# final_design_v1.net
KiCad netlist of a schematic drawn in EAGLE
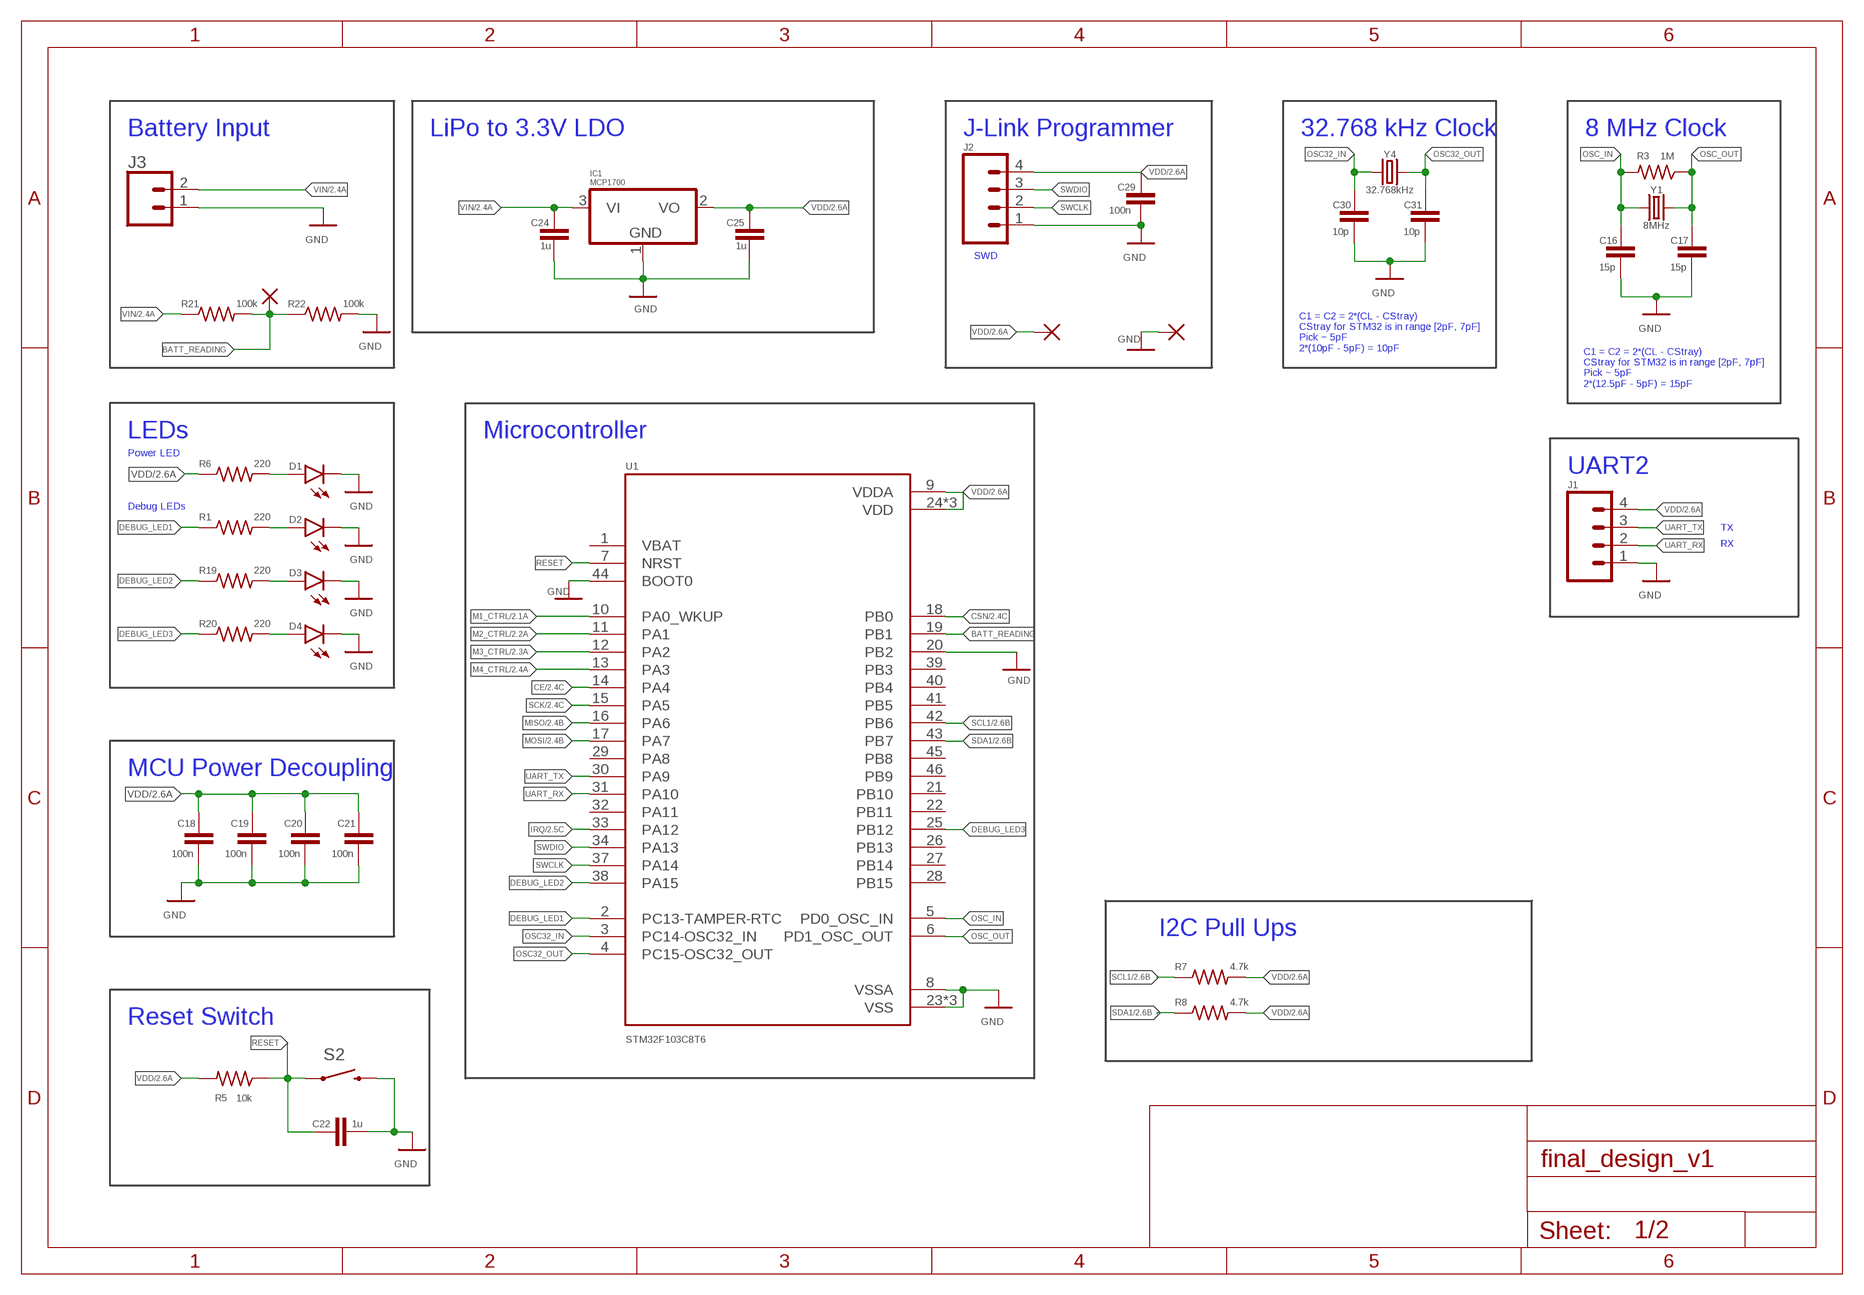
[diagram p0: schematic, sheet 1]
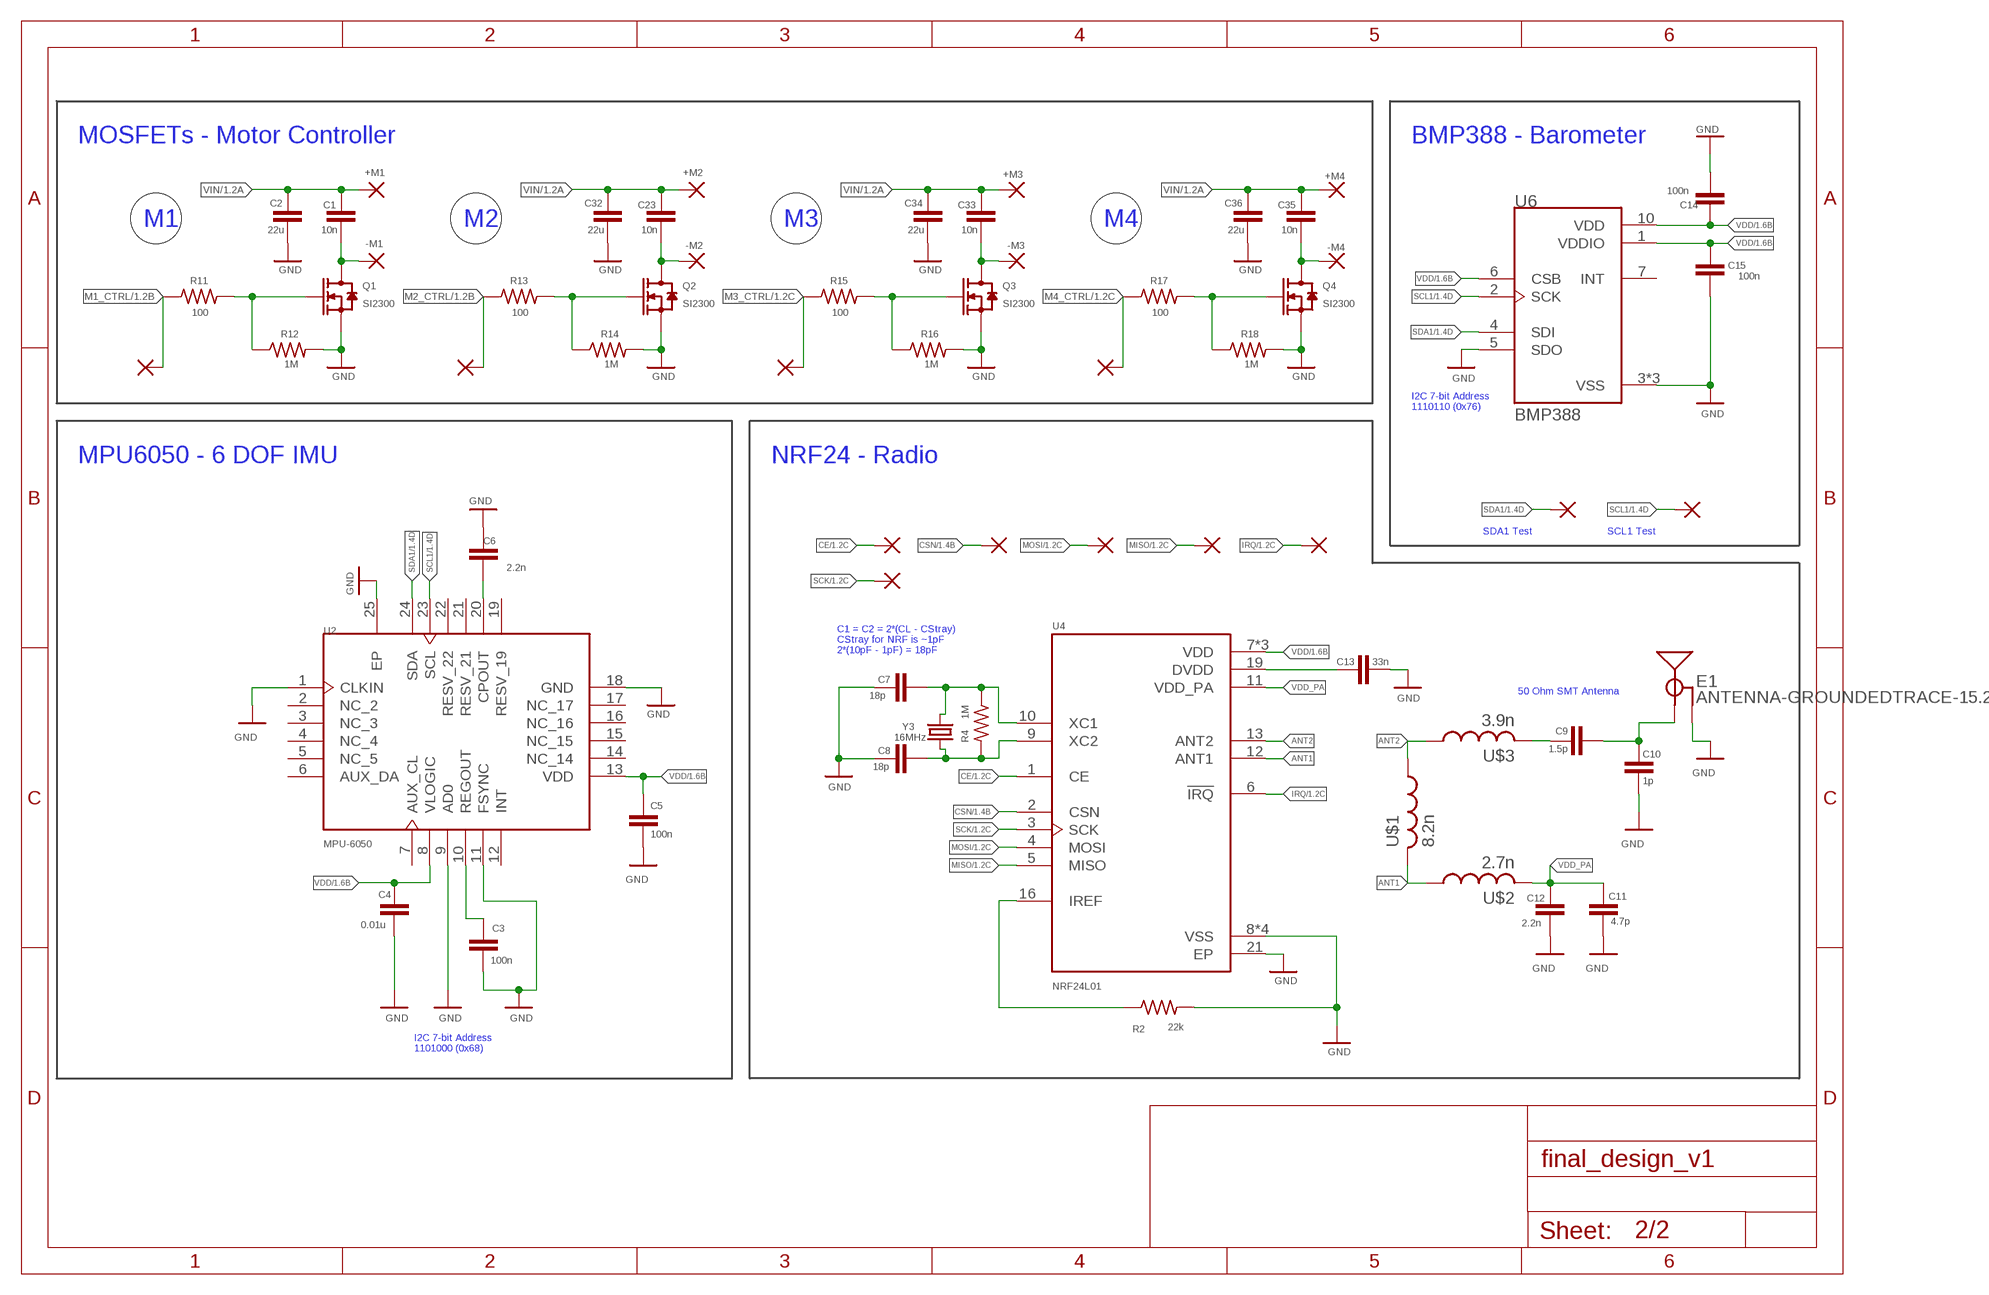
[diagram p1: schematic, sheet 2]

(export (version "E")
  (design (tool "Eeschema 10.0.6"))
  (components
    (comp (ref "+M1")
      (value "SMD2")
      (footprint "eagle-import:SMD1,27-2,54")
      (libsource (lib "eagle-import") (part "SMD2"))
    )
    (comp (ref "+M2")
      (value "SMD2")
      (footprint "eagle-import:SMD1,27-2,54")
      (libsource (lib "eagle-import") (part "SMD2"))
    )
    (comp (ref "+M3")
      (value "SMD2")
      (footprint "eagle-import:SMD1,27-2,54")
      (libsource (lib "eagle-import") (part "SMD2"))
    )
    (comp (ref "+M4")
      (value "SMD2")
      (footprint "eagle-import:SMD1,27-2,54")
      (libsource (lib "eagle-import") (part "SMD2"))
    )
    (comp (ref "+M5")
      (value "SMD2")
      (footprint "eagle-import:SMD1,27-2,54")
      (libsource (lib "eagle-import") (part "SMD2"))
    )
    (comp (ref "+M6")
      (value "SMD2")
      (footprint "eagle-import:SMD1,27-2,54")
      (libsource (lib "eagle-import") (part "SMD2"))
    )
    (comp (ref "+M7")
      (value "SMD2")
      (footprint "eagle-import:SMD1,27-2,54")
      (libsource (lib "eagle-import") (part "SMD2"))
    )
    (comp (ref "+M8")
      (value "SMD2")
      (footprint "eagle-import:SMD1,27-2,54")
      (libsource (lib "eagle-import") (part "SMD2"))
    )
    (comp (ref "+M9")
      (value "SMD2")
      (footprint "eagle-import:SMD1,27-2,54")
      (libsource (lib "eagle-import") (part "SMD2"))
    )
    (comp (ref "+M10")
      (value "SMD2")
      (footprint "eagle-import:SMD1,27-2,54")
      (libsource (lib "eagle-import") (part "SMD2"))
    )
    (comp (ref "+M13")
      (value "SMD2")
      (footprint "eagle-import:SMD1,27-2,54")
      (libsource (lib "eagle-import") (part "SMD2"))
    )
    (comp (ref "+M14")
      (value "SMD2")
      (footprint "eagle-import:SMD1,27-2,54")
      (libsource (lib "eagle-import") (part "SMD2"))
    )
    (comp (ref "+M15")
      (value "SMD2")
      (footprint "eagle-import:SMD1,27-2,54")
      (libsource (lib "eagle-import") (part "SMD2"))
    )
    (comp (ref "+M16")
      (value "SMD2")
      (footprint "eagle-import:SMD1,27-2,54")
      (libsource (lib "eagle-import") (part "SMD2"))
    )
    (comp (ref "+M17")
      (value "SMD2")
      (footprint "eagle-import:SMD1,27-2,54")
      (libsource (lib "eagle-import") (part "SMD2"))
    )
    (comp (ref "+M22")
      (value "SMD2")
      (footprint "eagle-import:SMD1,27-2,54")
      (libsource (lib "eagle-import") (part "SMD2"))
    )
    (comp (ref "-M1")
      (value "SMD2")
      (footprint "eagle-import:SMD1,27-2,54")
      (libsource (lib "eagle-import") (part "SMD2"))
    )
    (comp (ref "-M2")
      (value "SMD2")
      (footprint "eagle-import:SMD1,27-2,54")
      (libsource (lib "eagle-import") (part "SMD2"))
    )
    (comp (ref "-M3")
      (value "SMD2")
      (footprint "eagle-import:SMD1,27-2,54")
      (libsource (lib "eagle-import") (part "SMD2"))
    )
    (comp (ref "-M4")
      (value "SMD2")
      (footprint "eagle-import:SMD1,27-2,54")
      (libsource (lib "eagle-import") (part "SMD2"))
    )
    (comp (ref "C1")
      (value "10n")
      (footprint "eagle-import:CAP_0603")
      (fields
        (field (name "DIGIKEY_PART_NUMBER") "399-7814-2-ND")
        (field (name "MANUFACTURER") "KEMET")
        (field (name "MPN") "C0603C100C5GACTU")
        (field (name "CREATED_BY") "PCBLayout.com")
      )
      (libsource (lib "eagle-import") (part "C0603C100C5GACTU"))
    )
    (comp (ref "C2")
      (value "22u")
      (footprint "eagle-import:CAP_0603")
      (fields
        (field (name "DIGIKEY_PART_NUMBER") "399-7814-2-ND")
        (field (name "MANUFACTURER") "KEMET")
        (field (name "MPN") "C0603C100C5GACTU")
        (field (name "CREATED_BY") "PCBLayout.com")
      )
      (libsource (lib "eagle-import") (part "C0603C100C5GACTU"))
    )
    (comp (ref "C3")
      (value "100n")
      (footprint "eagle-import:CAP_0603")
      (fields
        (field (name "DIGIKEY_PART_NUMBER") "399-7814-2-ND")
        (field (name "MANUFACTURER") "KEMET")
        (field (name "MPN") "C0603C100C5GACTU")
        (field (name "CREATED_BY") "PCBLayout.com")
      )
      (libsource (lib "eagle-import") (part "C0603C100C5GACTU"))
    )
    (comp (ref "C4")
      (value "0.01u")
      (footprint "eagle-import:CAP_0603")
      (fields
        (field (name "DIGIKEY_PART_NUMBER") "399-7814-2-ND")
        (field (name "MANUFACTURER") "KEMET")
        (field (name "MPN") "C0603C100C5GACTU")
        (field (name "CREATED_BY") "PCBLayout.com")
      )
      (libsource (lib "eagle-import") (part "C0603C100C5GACTU"))
    )
    (comp (ref "C5")
      (value "100n")
      (footprint "eagle-import:CAP_0603")
      (fields
        (field (name "DIGIKEY_PART_NUMBER") "399-7814-2-ND")
        (field (name "MANUFACTURER") "KEMET")
        (field (name "MPN") "C0603C100C5GACTU")
        (field (name "CREATED_BY") "PCBLayout.com")
      )
      (libsource (lib "eagle-import") (part "C0603C100C5GACTU"))
    )
    (comp (ref "C6")
      (value "2.2n")
      (footprint "eagle-import:CAP_0603")
      (fields
        (field (name "DIGIKEY_PART_NUMBER") "399-7814-2-ND")
        (field (name "MANUFACTURER") "KEMET")
        (field (name "MPN") "C0603C100C5GACTU")
        (field (name "CREATED_BY") "PCBLayout.com")
      )
      (libsource (lib "eagle-import") (part "C0603C100C5GACTU"))
    )
    (comp (ref "C7")
      (value "18p")
      (footprint "eagle-import:CAP_0603")
      (fields
        (field (name "DIGIKEY_PART_NUMBER") "399-7814-2-ND")
        (field (name "MANUFACTURER") "KEMET")
        (field (name "MPN") "C0603C100C5GACTU")
        (field (name "CREATED_BY") "PCBLayout.com")
      )
      (libsource (lib "eagle-import") (part "C0603C100C5GACTU"))
    )
    (comp (ref "C8")
      (value "18p")
      (footprint "eagle-import:CAP_0603")
      (fields
        (field (name "DIGIKEY_PART_NUMBER") "399-7814-2-ND")
        (field (name "MANUFACTURER") "KEMET")
        (field (name "MPN") "C0603C100C5GACTU")
        (field (name "CREATED_BY") "PCBLayout.com")
      )
      (libsource (lib "eagle-import") (part "C0603C100C5GACTU"))
    )
    (comp (ref "C9")
      (value "1.5p")
      (footprint "eagle-import:CAP_0603")
      (fields
        (field (name "DIGIKEY_PART_NUMBER") "399-7814-2-ND")
        (field (name "MANUFACTURER") "KEMET")
        (field (name "MPN") "C0603C100C5GACTU")
        (field (name "CREATED_BY") "PCBLayout.com")
      )
      (libsource (lib "eagle-import") (part "C0603C100C5GACTU"))
    )
    (comp (ref "C10")
      (value "1p")
      (footprint "eagle-import:CAP_0603")
      (fields
        (field (name "DIGIKEY_PART_NUMBER") "399-7814-2-ND")
        (field (name "MANUFACTURER") "KEMET")
        (field (name "MPN") "C0603C100C5GACTU")
        (field (name "CREATED_BY") "PCBLayout.com")
      )
      (libsource (lib "eagle-import") (part "C0603C100C5GACTU"))
    )
    (comp (ref "C11")
      (value "4.7p")
      (footprint "eagle-import:CAP_0603")
      (fields
        (field (name "DIGIKEY_PART_NUMBER") "399-7814-2-ND")
        (field (name "MANUFACTURER") "KEMET")
        (field (name "MPN") "C0603C100C5GACTU")
        (field (name "CREATED_BY") "PCBLayout.com")
      )
      (libsource (lib "eagle-import") (part "C0603C100C5GACTU"))
    )
    (comp (ref "C12")
      (value "2.2n")
      (footprint "eagle-import:CAP_0603")
      (fields
        (field (name "DIGIKEY_PART_NUMBER") "399-7814-2-ND")
        (field (name "MANUFACTURER") "KEMET")
        (field (name "MPN") "C0603C100C5GACTU")
        (field (name "CREATED_BY") "PCBLayout.com")
      )
      (libsource (lib "eagle-import") (part "C0603C100C5GACTU"))
    )
    (comp (ref "C13")
      (value "33n")
      (footprint "eagle-import:CAP_0603")
      (fields
        (field (name "DIGIKEY_PART_NUMBER") "399-7814-2-ND")
        (field (name "MANUFACTURER") "KEMET")
        (field (name "MPN") "C0603C100C5GACTU")
        (field (name "CREATED_BY") "PCBLayout.com")
      )
      (libsource (lib "eagle-import") (part "C0603C100C5GACTU"))
    )
    (comp (ref "C14")
      (value "100n")
      (footprint "eagle-import:CAP_0603")
      (fields
        (field (name "DIGIKEY_PART_NUMBER") "399-7814-2-ND")
        (field (name "MANUFACTURER") "KEMET")
        (field (name "MPN") "C0603C100C5GACTU")
        (field (name "CREATED_BY") "PCBLayout.com")
      )
      (libsource (lib "eagle-import") (part "C0603C100C5GACTU"))
    )
    (comp (ref "C15")
      (value "100n")
      (footprint "eagle-import:CAP_0603")
      (fields
        (field (name "DIGIKEY_PART_NUMBER") "399-7814-2-ND")
        (field (name "MANUFACTURER") "KEMET")
        (field (name "MPN") "C0603C100C5GACTU")
        (field (name "CREATED_BY") "PCBLayout.com")
      )
      (libsource (lib "eagle-import") (part "C0603C100C5GACTU"))
    )
    (comp (ref "C23")
      (value "10n")
      (footprint "eagle-import:CAP_0603")
      (fields
        (field (name "DIGIKEY_PART_NUMBER") "399-7814-2-ND")
        (field (name "MANUFACTURER") "KEMET")
        (field (name "MPN") "C0603C100C5GACTU")
        (field (name "CREATED_BY") "PCBLayout.com")
      )
      (libsource (lib "eagle-import") (part "C0603C100C5GACTU"))
    )
    (comp (ref "C32")
      (value "22u")
      (footprint "eagle-import:CAP_0603")
      (fields
        (field (name "DIGIKEY_PART_NUMBER") "399-7814-2-ND")
        (field (name "MANUFACTURER") "KEMET")
        (field (name "MPN") "C0603C100C5GACTU")
        (field (name "CREATED_BY") "PCBLayout.com")
      )
      (libsource (lib "eagle-import") (part "C0603C100C5GACTU"))
    )
    (comp (ref "C33")
      (value "10n")
      (footprint "eagle-import:CAP_0603")
      (fields
        (field (name "DIGIKEY_PART_NUMBER") "399-7814-2-ND")
        (field (name "MANUFACTURER") "KEMET")
        (field (name "MPN") "C0603C100C5GACTU")
        (field (name "CREATED_BY") "PCBLayout.com")
      )
      (libsource (lib "eagle-import") (part "C0603C100C5GACTU"))
    )
    (comp (ref "C34")
      (value "22u")
      (footprint "eagle-import:CAP_0603")
      (fields
        (field (name "DIGIKEY_PART_NUMBER") "399-7814-2-ND")
        (field (name "MANUFACTURER") "KEMET")
        (field (name "MPN") "C0603C100C5GACTU")
        (field (name "CREATED_BY") "PCBLayout.com")
      )
      (libsource (lib "eagle-import") (part "C0603C100C5GACTU"))
    )
    (comp (ref "C35")
      (value "10n")
      (footprint "eagle-import:CAP_0603")
      (fields
        (field (name "DIGIKEY_PART_NUMBER") "399-7814-2-ND")
        (field (name "MANUFACTURER") "KEMET")
        (field (name "MPN") "C0603C100C5GACTU")
        (field (name "CREATED_BY") "PCBLayout.com")
      )
      (libsource (lib "eagle-import") (part "C0603C100C5GACTU"))
    )
    (comp (ref "C36")
      (value "22u")
      (footprint "eagle-import:CAP_0603")
      (fields
        (field (name "DIGIKEY_PART_NUMBER") "399-7814-2-ND")
        (field (name "MANUFACTURER") "KEMET")
        (field (name "MPN") "C0603C100C5GACTU")
        (field (name "CREATED_BY") "PCBLayout.com")
      )
      (libsource (lib "eagle-import") (part "C0603C100C5GACTU"))
    )
    (comp (ref "E1")
      (value "ANTENNA-GROUNDEDTRACE-15.2MM")
      (footprint "eagle-import:TRACE_ANTENNA_2.4GHZ_15.2MM")
      (libsource (lib "eagle-import") (part "ANTENNA-GROUNDEDTRACE-15.2MM"))
    )
    (comp (ref "Q1")
      (value "SI2300")
      (footprint "eagle-import:SOT-23")
      (fields (field (name "MPN") "2N7002,215"))
      (libsource (lib "eagle-import") (part "SMD-MOSFET-N-CH-60V-300MA-LOGIC-LEVEL-FET-2N7002(SOT-23)"))
    )
    (comp (ref "Q2")
      (value "SI2300")
      (footprint "eagle-import:SOT-23")
      (fields (field (name "MPN") "2N7002,215"))
      (libsource (lib "eagle-import") (part "SMD-MOSFET-N-CH-60V-300MA-LOGIC-LEVEL-FET-2N7002(SOT-23)"))
    )
    (comp (ref "Q3")
      (value "SI2300")
      (footprint "eagle-import:SOT-23")
      (fields (field (name "MPN") "2N7002,215"))
      (libsource (lib "eagle-import") (part "SMD-MOSFET-N-CH-60V-300MA-LOGIC-LEVEL-FET-2N7002(SOT-23)"))
    )
    (comp (ref "Q4")
      (value "SI2300")
      (footprint "eagle-import:SOT-23")
      (fields (field (name "MPN") "2N7002,215"))
      (libsource (lib "eagle-import") (part "SMD-MOSFET-N-CH-60V-300MA-LOGIC-LEVEL-FET-2N7002(SOT-23)"))
    )
    (comp (ref "R2")
      (value "22k")
      (footprint "eagle-import:RES_0603")
      (fields
        (field (name "DIGIKEY_PART_NUMBER") "311-0.0GRTR-ND")
        (field (name "MANUFACTURER") "Yageo")
        (field (name "MPN") "RC0603JR-070RL")
        (field (name "CREATED_BY") "PCBLayout.com")
      )
      (libsource (lib "eagle-import") (part "RC0603JR-070RL"))
    )
    (comp (ref "R4")
      (value "1M")
      (footprint "eagle-import:RES_0603")
      (fields
        (field (name "DIGIKEY_PART_NUMBER") "311-0.0GRTR-ND")
        (field (name "MANUFACTURER") "Yageo")
        (field (name "MPN") "RC0603JR-070RL")
        (field (name "CREATED_BY") "PCBLayout.com")
      )
      (libsource (lib "eagle-import") (part "RC0603JR-070RL"))
    )
    (comp (ref "R11")
      (value "100")
      (footprint "eagle-import:RES_0603")
      (fields
        (field (name "DIGIKEY_PART_NUMBER") "311-0.0GRTR-ND")
        (field (name "MANUFACTURER") "Yageo")
        (field (name "MPN") "RC0603JR-070RL")
        (field (name "CREATED_BY") "PCBLayout.com")
      )
      (libsource (lib "eagle-import") (part "RC0603JR-070RL"))
    )
    (comp (ref "R12")
      (value "1M")
      (footprint "eagle-import:RES_0603")
      (fields
        (field (name "DIGIKEY_PART_NUMBER") "311-0.0GRTR-ND")
        (field (name "MANUFACTURER") "Yageo")
        (field (name "MPN") "RC0603JR-070RL")
        (field (name "CREATED_BY") "PCBLayout.com")
      )
      (libsource (lib "eagle-import") (part "RC0603JR-070RL"))
    )
    (comp (ref "R13")
      (value "100")
      (footprint "eagle-import:RES_0603")
      (fields
        (field (name "DIGIKEY_PART_NUMBER") "311-0.0GRTR-ND")
        (field (name "MANUFACTURER") "Yageo")
        (field (name "MPN") "RC0603JR-070RL")
        (field (name "CREATED_BY") "PCBLayout.com")
      )
      (libsource (lib "eagle-import") (part "RC0603JR-070RL"))
    )
    (comp (ref "R14")
      (value "1M")
      (footprint "eagle-import:RES_0603")
      (fields
        (field (name "DIGIKEY_PART_NUMBER") "311-0.0GRTR-ND")
        (field (name "MANUFACTURER") "Yageo")
        (field (name "MPN") "RC0603JR-070RL")
        (field (name "CREATED_BY") "PCBLayout.com")
      )
      (libsource (lib "eagle-import") (part "RC0603JR-070RL"))
    )
    (comp (ref "R15")
      (value "100")
      (footprint "eagle-import:RES_0603")
      (fields
        (field (name "DIGIKEY_PART_NUMBER") "311-0.0GRTR-ND")
        (field (name "MANUFACTURER") "Yageo")
        (field (name "MPN") "RC0603JR-070RL")
        (field (name "CREATED_BY") "PCBLayout.com")
      )
      (libsource (lib "eagle-import") (part "RC0603JR-070RL"))
    )
    (comp (ref "R16")
      (value "1M")
      (footprint "eagle-import:RES_0603")
      (fields
        (field (name "DIGIKEY_PART_NUMBER") "311-0.0GRTR-ND")
        (field (name "MANUFACTURER") "Yageo")
        (field (name "MPN") "RC0603JR-070RL")
        (field (name "CREATED_BY") "PCBLayout.com")
      )
      (libsource (lib "eagle-import") (part "RC0603JR-070RL"))
    )
    (comp (ref "R17")
      (value "100")
      (footprint "eagle-import:RES_0603")
      (fields
        (field (name "DIGIKEY_PART_NUMBER") "311-0.0GRTR-ND")
        (field (name "MANUFACTURER") "Yageo")
        (field (name "MPN") "RC0603JR-070RL")
        (field (name "CREATED_BY") "PCBLayout.com")
      )
      (libsource (lib "eagle-import") (part "RC0603JR-070RL"))
    )
    (comp (ref "R18")
      (value "1M")
      (footprint "eagle-import:RES_0603")
      (fields
        (field (name "DIGIKEY_PART_NUMBER") "311-0.0GRTR-ND")
        (field (name "MANUFACTURER") "Yageo")
        (field (name "MPN") "RC0603JR-070RL")
        (field (name "CREATED_BY") "PCBLayout.com")
      )
      (libsource (lib "eagle-import") (part "RC0603JR-070RL"))
    )
    (comp (ref "U$1")
      (value "8.2n")
      (footprint "eagle-import:RESC0603_N")
      (libsource (lib "eagle-import") (part "INDUCTOR_0603_N"))
    )
    (comp (ref "U$2")
      (value "2.7n")
      (footprint "eagle-import:RESC0603_N")
      (libsource (lib "eagle-import") (part "INDUCTOR_0603_N"))
    )
    (comp (ref "U$3")
      (value "3.9n")
      (footprint "eagle-import:RESC0603_N")
      (libsource (lib "eagle-import") (part "INDUCTOR_0603_N"))
    )
    (comp (ref "U2")
      (value "MPU-6050")
      (footprint "eagle-import:24-VFQFN")
      (fields
        (field (name "DIGIKEY_PART_NUMBER") "1428-1007-1-ND")
        (field (name "MANUFACTURER") "TDK InvenSense")
        (field (name "CREATED_BY") "PCBLayout.com")
      )
      (libsource (lib "eagle-import") (part "MPU-6050"))
    )
    (comp (ref "U4")
      (value "NRF24L01")
      (footprint "eagle-import:QFN50P400X400X95-21N")
      (fields (field (name "MF") "Nordic"))
      (libsource (lib "eagle-import") (part "NRF24L01"))
    )
    (comp (ref "U6")
      (value "BMP388")
      (footprint "eagle-import:PQFN50P200X200X80-10N")
      (fields (field (name "DIGI-KEY_PART_NUMBER") "828-1079-1-ND") (field (name "MF") "Bosch Sensortec"))
      (libsource (lib "eagle-import") (part "BMP388"))
    )
    (comp (ref "Y3")
      (value "16MHz")
      (footprint "eagle-import:CRYSTAL-SMD-5X3.2-4PAD")
      (libsource (lib "eagle-import") (part "CRYSTAL-16MHZSMD-5X3.2"))
    )
    (comp (ref "+M18")
      (value "SMD2")
      (footprint "eagle-import:SMD1,27-2,54")
      (libsource (lib "eagle-import") (part "SMD2"))
    )
    (comp (ref "+M19")
      (value "SMD2")
      (footprint "eagle-import:SMD1,27-2,54")
      (libsource (lib "eagle-import") (part "SMD2"))
    )
    (comp (ref "+M20")
      (value "SMD2")
      (footprint "eagle-import:SMD1,27-2,54")
      (libsource (lib "eagle-import") (part "SMD2"))
    )
    (comp (ref "C16")
      (value "15p")
      (footprint "eagle-import:CAP_0603")
      (fields
        (field (name "DIGIKEY_PART_NUMBER") "399-7814-2-ND")
        (field (name "MANUFACTURER") "KEMET")
        (field (name "MPN") "C0603C100C5GACTU")
        (field (name "CREATED_BY") "PCBLayout.com")
      )
      (libsource (lib "eagle-import") (part "C0603C100C5GACTU"))
    )
    (comp (ref "C17")
      (value "15p")
      (footprint "eagle-import:CAP_0603")
      (fields
        (field (name "DIGIKEY_PART_NUMBER") "399-7814-2-ND")
        (field (name "MANUFACTURER") "KEMET")
        (field (name "MPN") "C0603C100C5GACTU")
        (field (name "CREATED_BY") "PCBLayout.com")
      )
      (libsource (lib "eagle-import") (part "C0603C100C5GACTU"))
    )
    (comp (ref "C18")
      (value "100n")
      (footprint "eagle-import:CAP_0603")
      (fields
        (field (name "DIGIKEY_PART_NUMBER") "399-7814-2-ND")
        (field (name "MANUFACTURER") "KEMET")
        (field (name "MPN") "C0603C100C5GACTU")
        (field (name "CREATED_BY") "PCBLayout.com")
      )
      (libsource (lib "eagle-import") (part "C0603C100C5GACTU"))
    )
    (comp (ref "C19")
      (value "100n")
      (footprint "eagle-import:CAP_0603")
      (fields
        (field (name "DIGIKEY_PART_NUMBER") "399-7814-2-ND")
        (field (name "MANUFACTURER") "KEMET")
        (field (name "MPN") "C0603C100C5GACTU")
        (field (name "CREATED_BY") "PCBLayout.com")
      )
      (libsource (lib "eagle-import") (part "C0603C100C5GACTU"))
    )
    (comp (ref "C20")
      (value "100n")
      (footprint "eagle-import:CAP_0603")
      (fields
        (field (name "DIGIKEY_PART_NUMBER") "399-7814-2-ND")
        (field (name "MANUFACTURER") "KEMET")
        (field (name "MPN") "C0603C100C5GACTU")
        (field (name "CREATED_BY") "PCBLayout.com")
      )
      (libsource (lib "eagle-import") (part "C0603C100C5GACTU"))
    )
    (comp (ref "C21")
      (value "100n")
      (footprint "eagle-import:CAP_0603")
      (fields
        (field (name "DIGIKEY_PART_NUMBER") "399-7814-2-ND")
        (field (name "MANUFACTURER") "KEMET")
        (field (name "MPN") "C0603C100C5GACTU")
        (field (name "CREATED_BY") "PCBLayout.com")
      )
      (libsource (lib "eagle-import") (part "C0603C100C5GACTU"))
    )
    (comp (ref "C22")
      (value "1u")
      (footprint "eagle-import:CAP_0603")
      (fields
        (field (name "DIGIKEY_PART_NUMBER") "399-7814-2-ND")
        (field (name "MANUFACTURER") "KEMET")
        (field (name "MPN") "C0603C100C5GACTU")
        (field (name "CREATED_BY") "PCBLayout.com")
      )
      (libsource (lib "eagle-import") (part "C0603C100C5GACTU"))
    )
    (comp (ref "C24")
      (value "1u")
      (footprint "eagle-import:CAP_0603")
      (fields
        (field (name "DIGIKEY_PART_NUMBER") "399-7814-2-ND")
        (field (name "MANUFACTURER") "KEMET")
        (field (name "MPN") "C0603C100C5GACTU")
        (field (name "CREATED_BY") "PCBLayout.com")
      )
      (libsource (lib "eagle-import") (part "C0603C100C5GACTU"))
    )
    (comp (ref "C25")
      (value "1u")
      (footprint "eagle-import:CAP_0603")
      (fields
        (field (name "DIGIKEY_PART_NUMBER") "399-7814-2-ND")
        (field (name "MANUFACTURER") "KEMET")
        (field (name "MPN") "C0603C100C5GACTU")
        (field (name "CREATED_BY") "PCBLayout.com")
      )
      (libsource (lib "eagle-import") (part "C0603C100C5GACTU"))
    )
    (comp (ref "C29")
      (value "100n")
      (footprint "eagle-import:CAP_0603")
      (fields
        (field (name "DIGIKEY_PART_NUMBER") "399-7814-2-ND")
        (field (name "MANUFACTURER") "KEMET")
        (field (name "MPN") "C0603C100C5GACTU")
        (field (name "CREATED_BY") "PCBLayout.com")
      )
      (libsource (lib "eagle-import") (part "C0603C100C5GACTU"))
    )
    (comp (ref "C30")
      (value "10p")
      (footprint "eagle-import:CAP_0603")
      (fields
        (field (name "DIGIKEY_PART_NUMBER") "399-7814-2-ND")
        (field (name "MANUFACTURER") "KEMET")
        (field (name "MPN") "C0603C100C5GACTU")
        (field (name "CREATED_BY") "PCBLayout.com")
      )
      (libsource (lib "eagle-import") (part "C0603C100C5GACTU"))
    )
    (comp (ref "C31")
      (value "10p")
      (footprint "eagle-import:CAP_0603")
      (fields
        (field (name "DIGIKEY_PART_NUMBER") "399-7814-2-ND")
        (field (name "MANUFACTURER") "KEMET")
        (field (name "MPN") "C0603C100C5GACTU")
        (field (name "CREATED_BY") "PCBLayout.com")
      )
      (libsource (lib "eagle-import") (part "C0603C100C5GACTU"))
    )
    (comp (ref "D1")
      (value "LED0603")
      (footprint "eagle-import:LED-0603")
      (libsource (lib "eagle-import") (part "LED0603"))
    )
    (comp (ref "D2")
      (value "LED0603")
      (footprint "eagle-import:LED-0603")
      (libsource (lib "eagle-import") (part "LED0603"))
    )
    (comp (ref "D3")
      (value "LED0603")
      (footprint "eagle-import:LED-0603")
      (libsource (lib "eagle-import") (part "LED0603"))
    )
    (comp (ref "D4")
      (value "LED0603")
      (footprint "eagle-import:LED-0603")
      (libsource (lib "eagle-import") (part "LED0603"))
    )
    (comp (ref "IC1")
      (value "MCP1700")
      (footprint "eagle-import:SOT23")
      (libsource (lib "eagle-import") (part "MCP1703CB"))
    )
    (comp (ref "J1")
      (value "CONN_04")
      (footprint "eagle-import:1X04")
      (libsource (lib "eagle-import") (part "CONN_04"))
    )
    (comp (ref "J2")
      (value "CONN_04")
      (footprint "eagle-import:1X04")
      (libsource (lib "eagle-import") (part "CONN_04"))
    )
    (comp (ref "J3")
      (value "CONN_02")
      (footprint "eagle-import:1X02")
      (libsource (lib "eagle-import") (part "CONN_02"))
    )
    (comp (ref "R1")
      (value "220")
      (footprint "eagle-import:RES_0603")
      (fields
        (field (name "DIGIKEY_PART_NUMBER") "311-0.0GRTR-ND")
        (field (name "MANUFACTURER") "Yageo")
        (field (name "MPN") "RC0603JR-070RL")
        (field (name "CREATED_BY") "PCBLayout.com")
      )
      (libsource (lib "eagle-import") (part "RC0603JR-070RL"))
    )
    (comp (ref "R3")
      (value "1M")
      (footprint "eagle-import:RES_0603")
      (fields
        (field (name "DIGIKEY_PART_NUMBER") "311-0.0GRTR-ND")
        (field (name "MANUFACTURER") "Yageo")
        (field (name "MPN") "RC0603JR-070RL")
        (field (name "CREATED_BY") "PCBLayout.com")
      )
      (libsource (lib "eagle-import") (part "RC0603JR-070RL"))
    )
    (comp (ref "R5")
      (value "10k")
      (footprint "eagle-import:RES_0603")
      (fields
        (field (name "DIGIKEY_PART_NUMBER") "311-0.0GRTR-ND")
        (field (name "MANUFACTURER") "Yageo")
        (field (name "MPN") "RC0603JR-070RL")
        (field (name "CREATED_BY") "PCBLayout.com")
      )
      (libsource (lib "eagle-import") (part "RC0603JR-070RL"))
    )
    (comp (ref "R6")
      (value "220")
      (footprint "eagle-import:RES_0603")
      (fields
        (field (name "DIGIKEY_PART_NUMBER") "311-0.0GRTR-ND")
        (field (name "MANUFACTURER") "Yageo")
        (field (name "MPN") "RC0603JR-070RL")
        (field (name "CREATED_BY") "PCBLayout.com")
      )
      (libsource (lib "eagle-import") (part "RC0603JR-070RL"))
    )
    (comp (ref "R7")
      (value "4.7k")
      (footprint "eagle-import:RES_0603")
      (fields
        (field (name "DIGIKEY_PART_NUMBER") "311-0.0GRTR-ND")
        (field (name "MANUFACTURER") "Yageo")
        (field (name "MPN") "RC0603JR-070RL")
        (field (name "CREATED_BY") "PCBLayout.com")
      )
      (libsource (lib "eagle-import") (part "RC0603JR-070RL"))
    )
    (comp (ref "R8")
      (value "4.7k")
      (footprint "eagle-import:RES_0603")
      (fields
        (field (name "DIGIKEY_PART_NUMBER") "311-0.0GRTR-ND")
        (field (name "MANUFACTURER") "Yageo")
        (field (name "MPN") "RC0603JR-070RL")
        (field (name "CREATED_BY") "PCBLayout.com")
      )
      (libsource (lib "eagle-import") (part "RC0603JR-070RL"))
    )
    (comp (ref "R19")
      (value "220")
      (footprint "eagle-import:RES_0603")
      (fields
        (field (name "DIGIKEY_PART_NUMBER") "311-0.0GRTR-ND")
        (field (name "MANUFACTURER") "Yageo")
        (field (name "MPN") "RC0603JR-070RL")
        (field (name "CREATED_BY") "PCBLayout.com")
      )
      (libsource (lib "eagle-import") (part "RC0603JR-070RL"))
    )
    (comp (ref "R20")
      (value "220")
      (footprint "eagle-import:RES_0603")
      (fields
        (field (name "DIGIKEY_PART_NUMBER") "311-0.0GRTR-ND")
        (field (name "MANUFACTURER") "Yageo")
        (field (name "MPN") "RC0603JR-070RL")
        (field (name "CREATED_BY") "PCBLayout.com")
      )
      (libsource (lib "eagle-import") (part "RC0603JR-070RL"))
    )
    (comp (ref "R21")
      (value "100k")
      (footprint "eagle-import:RES_0603")
      (fields
        (field (name "DIGIKEY_PART_NUMBER") "311-0.0GRTR-ND")
        (field (name "MANUFACTURER") "Yageo")
        (field (name "MPN") "RC0603JR-070RL")
        (field (name "CREATED_BY") "PCBLayout.com")
      )
      (libsource (lib "eagle-import") (part "RC0603JR-070RL"))
    )
    (comp (ref "R22")
      (value "100k")
      (footprint "eagle-import:RES_0603")
      (fields
        (field (name "DIGIKEY_PART_NUMBER") "311-0.0GRTR-ND")
        (field (name "MANUFACTURER") "Yageo")
        (field (name "MPN") "RC0603JR-070RL")
        (field (name "CREATED_BY") "PCBLayout.com")
      )
      (libsource (lib "eagle-import") (part "RC0603JR-070RL"))
    )
    (comp (ref "S2")
      (value "RS032G05A3SM-SPST-MOMENTARY-SWSMD-1101NE")
      (footprint "eagle-import:TACTILE-SWITCH-1101NE")
      (libsource (lib "eagle-import") (part "RS032G05A3SM-SPST-MOMENTARY-SWSMD-1101NE"))
    )
    (comp (ref "U1")
      (value "STM32F103C8T6")
      (footprint "eagle-import:QFP50P900X900X160-48N")
      (fields (field (name "MF") "STMicroelectronics") (field (name "SPICEPREFIX") "X"))
      (libsource (lib "eagle-import") (part "STM32F103C8T6"))
    )
    (comp (ref "Y1")
      (value "8MHz")
      (footprint "eagle-import:CRYSTAL-SMD-5X3.2-4PAD")
      (libsource (lib "eagle-import") (part "CRYSTAL-8MHZSMD-5X3.2"))
    )
    (comp (ref "Y4")
      (value "32.768kHz")
      (footprint "eagle-import:CRYSTAL-SMD-3.2X1.5MM")
      (libsource (lib "eagle-import") (part "CRYSTAL-32.768KHZSMD-3.2X1.5"))
    )
  )
  (nets
    (net (code "1") (name "ANT1") (class "Default")
      (node (ref "U$1") (pin "2") (pinfunction "2_2") (pintype "passive"))
      (node (ref "U$2") (pin "1") (pinfunction "1_1") (pintype "passive"))
      (node (ref "U4") (pin "12") (pinfunction "ANT1_12") (pintype "bidirectional"))
    )
    (net (code "2") (name "ANT2") (class "Default")
      (node (ref "U$1") (pin "1") (pinfunction "1_1") (pintype "passive"))
      (node (ref "U$3") (pin "1") (pinfunction "1_1") (pintype "passive"))
      (node (ref "U4") (pin "13") (pinfunction "ANT2_13") (pintype "bidirectional"))
    )
    (net (code "3") (name "BATT_READING") (class "Default")
      (node (ref "+M20") (pin "1") (pinfunction "P_1") (pintype "passive"))
      (node (ref "R21") (pin "2") (pinfunction "2_2") (pintype "passive"))
      (node (ref "R22") (pin "1") (pinfunction "1_1") (pintype "passive"))
      (node (ref "U1") (pin "19") (pinfunction "PB1_19") (pintype "bidirectional"))
    )
    (net (code "4") (name "CE") (class "Default")
      (node (ref "+M13") (pin "1") (pinfunction "P_1") (pintype "passive"))
      (node (ref "U1") (pin "14") (pinfunction "PA4_14") (pintype "bidirectional"))
      (node (ref "U4") (pin "1") (pinfunction "CE_1") (pintype "input"))
    )
    (net (code "5") (name "CSN") (class "Default")
      (node (ref "+M14") (pin "1") (pinfunction "P_1") (pintype "passive"))
      (node (ref "U1") (pin "18") (pinfunction "PB0_18") (pintype "bidirectional"))
      (node (ref "U4") (pin "2") (pinfunction "CSN_2") (pintype "input"))
    )
    (net (code "6") (name "DEBUG_LED1") (class "Default")
      (node (ref "R1") (pin "1") (pinfunction "1_1") (pintype "passive"))
      (node (ref "U1") (pin "2") (pinfunction "PC13-TAMPER-RTC_2") (pintype "bidirectional"))
    )
    (net (code "7") (name "DEBUG_LED2") (class "Default")
      (node (ref "R19") (pin "1") (pinfunction "1_1") (pintype "passive"))
      (node (ref "U1") (pin "38") (pinfunction "PA15_38") (pintype "bidirectional"))
    )
    (net (code "8") (name "DEBUG_LED3") (class "Default")
      (node (ref "R20") (pin "1") (pinfunction "1_1") (pintype "passive"))
      (node (ref "U1") (pin "25") (pinfunction "PB12_25") (pintype "bidirectional"))
    )
    (net (code "9") (name "GND") (class "Default")
      (node (ref "+M19") (pin "1") (pinfunction "P_1") (pintype "passive"))
      (node (ref "C10") (pin "1") (pinfunction "1_1") (pintype "passive"))
      (node (ref "C11") (pin "1") (pinfunction "1_1") (pintype "passive"))
      (node (ref "C12") (pin "1") (pinfunction "1_1") (pintype "passive"))
      (node (ref "C13") (pin "2") (pinfunction "2_2") (pintype "passive"))
      (node (ref "C14") (pin "2") (pinfunction "2_2") (pintype "passive"))
      (node (ref "C15") (pin "1") (pinfunction "1_1") (pintype "passive"))
      (node (ref "C16") (pin "2") (pinfunction "2_2") (pintype "passive"))
      (node (ref "C17") (pin "2") (pinfunction "2_2") (pintype "passive"))
      (node (ref "C18") (pin "2") (pinfunction "2_2") (pintype "passive"))
      (node (ref "C19") (pin "2") (pinfunction "2_2") (pintype "passive"))
      (node (ref "C2") (pin "1") (pinfunction "1_1") (pintype "passive"))
      (node (ref "C20") (pin "2") (pinfunction "2_2") (pintype "passive"))
      (node (ref "C21") (pin "2") (pinfunction "2_2") (pintype "passive"))
      (node (ref "C22") (pin "2") (pinfunction "2_2") (pintype "passive"))
      (node (ref "C24") (pin "2") (pinfunction "2_2") (pintype "passive"))
      (node (ref "C25") (pin "2") (pinfunction "2_2") (pintype "passive"))
      (node (ref "C29") (pin "2") (pinfunction "2_2") (pintype "passive"))
      (node (ref "C3") (pin "2") (pinfunction "2_2") (pintype "passive"))
      (node (ref "C30") (pin "2") (pinfunction "2_2") (pintype "passive"))
      (node (ref "C31") (pin "2") (pinfunction "2_2") (pintype "passive"))
      (node (ref "C32") (pin "1") (pinfunction "1_1") (pintype "passive"))
      (node (ref "C34") (pin "1") (pinfunction "1_1") (pintype "passive"))
      (node (ref "C36") (pin "1") (pinfunction "1_1") (pintype "passive"))
      (node (ref "C4") (pin "2") (pinfunction "2_2") (pintype "passive"))
      (node (ref "C5") (pin "2") (pinfunction "2_2") (pintype "passive"))
      (node (ref "C6") (pin "2") (pinfunction "2_2") (pintype "passive"))
      (node (ref "C7") (pin "2") (pinfunction "2_2") (pintype "passive"))
      (node (ref "C8") (pin "2") (pinfunction "2_2") (pintype "passive"))
      (node (ref "D1") (pin "C") (pinfunction "C_C") (pintype "passive"))
      (node (ref "D2") (pin "C") (pinfunction "C_C") (pintype "passive"))
      (node (ref "D3") (pin "C") (pinfunction "C_C") (pintype "passive"))
      (node (ref "D4") (pin "C") (pinfunction "C_C") (pintype "passive"))
      (node (ref "E1") (pin "GND") (pinfunction "GND_GND") (pintype "bidirectional"))
      (node (ref "IC1") (pin "1") (pinfunction "GND_1") (pintype "passive"))
      (node (ref "J1") (pin "1") (pinfunction "1_1") (pintype "passive"))
      (node (ref "J2") (pin "1") (pinfunction "1_1") (pintype "passive"))
      (node (ref "J3") (pin "1") (pinfunction "1_1") (pintype "passive"))
      (node (ref "Q1") (pin "2") (pinfunction "S_2") (pintype "passive"))
      (node (ref "Q2") (pin "2") (pinfunction "S_2") (pintype "passive"))
      (node (ref "Q3") (pin "2") (pinfunction "S_2") (pintype "passive"))
      (node (ref "Q4") (pin "2") (pinfunction "S_2") (pintype "passive"))
      (node (ref "R12") (pin "2") (pinfunction "2_2") (pintype "passive"))
      (node (ref "R14") (pin "2") (pinfunction "2_2") (pintype "passive"))
      (node (ref "R16") (pin "2") (pinfunction "2_2") (pintype "passive"))
      (node (ref "R18") (pin "2") (pinfunction "2_2") (pintype "passive"))
      (node (ref "R2") (pin "2") (pinfunction "2_2") (pintype "passive"))
      (node (ref "R22") (pin "2") (pinfunction "2_2") (pintype "passive"))
      (node (ref "S2") (pin "2") (pinfunction "2_2") (pintype "passive"))
      (node (ref "U1") (pin "20") (pinfunction "PB2_20") (pintype "bidirectional"))
      (node (ref "U1") (pin "23") (pinfunction "VSS_23") (pintype "power_in"))
      (node (ref "U1") (pin "35") (pinfunction "VSS_35") (pintype "power_in"))
      (node (ref "U1") (pin "44") (pinfunction "BOOT0_44") (pintype "input"))
      (node (ref "U1") (pin "47") (pinfunction "VSS_47") (pintype "power_in"))
      (node (ref "U1") (pin "8") (pinfunction "VSSA_8") (pintype "power_in"))
      (node (ref "U2") (pin "1") (pinfunction "CLKIN_1") (pintype "input"))
      (node (ref "U2") (pin "11") (pinfunction "FSYNC_11") (pintype "input"))
      (node (ref "U2") (pin "18") (pinfunction "GND_18") (pintype "power_in"))
      (node (ref "U2") (pin "25") (pinfunction "EP_25") (pintype "power_in"))
      (node (ref "U2") (pin "9") (pinfunction "AD0_9") (pintype "bidirectional"))
      (node (ref "U4") (pin "14") (pinfunction "VSS_14") (pintype "power_in"))
      (node (ref "U4") (pin "17") (pinfunction "VSS_17") (pintype "power_in"))
      (node (ref "U4") (pin "20") (pinfunction "VSS_20") (pintype "power_in"))
      (node (ref "U4") (pin "21") (pinfunction "EP_21") (pintype "power_in"))
      (node (ref "U4") (pin "8") (pinfunction "VSS_8") (pintype "power_in"))
      (node (ref "U6") (pin "3") (pinfunction "VSS_3") (pintype "power_in"))
      (node (ref "U6") (pin "5") (pinfunction "SDO_5") (pintype "bidirectional"))
      (node (ref "U6") (pin "8") (pinfunction "VSS_8") (pintype "power_in"))
      (node (ref "U6") (pin "9") (pinfunction "VSS_9") (pintype "power_in"))
    )
    (net (code "10") (name "IRQ") (class "Default")
      (node (ref "+M17") (pin "1") (pinfunction "P_1") (pintype "passive"))
      (node (ref "U1") (pin "33") (pinfunction "PA12_33") (pintype "bidirectional"))
      (node (ref "U4") (pin "6") (pinfunction "~{IRQ}_6") (pintype "output"))
    )
    (net (code "11") (name "M1_CTRL") (class "Default")
      (node (ref "+M10") (pin "1") (pinfunction "P_1") (pintype "passive"))
      (node (ref "R11") (pin "1") (pinfunction "1_1") (pintype "passive"))
      (node (ref "U1") (pin "10") (pinfunction "PA0_WKUP_10") (pintype "bidirectional"))
    )
    (net (code "12") (name "M2_CTRL") (class "Default")
      (node (ref "+M9") (pin "1") (pinfunction "P_1") (pintype "passive"))
      (node (ref "R13") (pin "1") (pinfunction "1_1") (pintype "passive"))
      (node (ref "U1") (pin "11") (pinfunction "PA1_11") (pintype "bidirectional"))
    )
    (net (code "13") (name "M3_CTRL") (class "Default")
      (node (ref "+M8") (pin "1") (pinfunction "P_1") (pintype "passive"))
      (node (ref "R15") (pin "1") (pinfunction "1_1") (pintype "passive"))
      (node (ref "U1") (pin "12") (pinfunction "PA2_12") (pintype "bidirectional"))
    )
    (net (code "14") (name "M4_CTRL") (class "Default")
      (node (ref "+M7") (pin "1") (pinfunction "P_1") (pintype "passive"))
      (node (ref "R17") (pin "1") (pinfunction "1_1") (pintype "passive"))
      (node (ref "U1") (pin "13") (pinfunction "PA3_13") (pintype "bidirectional"))
    )
    (net (code "15") (name "MISO") (class "Default")
      (node (ref "+M16") (pin "1") (pinfunction "P_1") (pintype "passive"))
      (node (ref "U1") (pin "16") (pinfunction "PA6_16") (pintype "bidirectional"))
      (node (ref "U4") (pin "5") (pinfunction "MISO_5") (pintype "output"))
    )
    (net (code "16") (name "MOSI") (class "Default")
      (node (ref "+M15") (pin "1") (pinfunction "P_1") (pintype "passive"))
      (node (ref "U1") (pin "17") (pinfunction "PA7_17") (pintype "bidirectional"))
      (node (ref "U4") (pin "4") (pinfunction "MOSI_4") (pintype "input"))
    )
    (net (code "17") (name "Net-(-M1-P)") (class "Default")
      (node (ref "-M1") (pin "1") (pinfunction "P_1") (pintype "passive"))
      (node (ref "C1") (pin "1") (pinfunction "1_1") (pintype "passive"))
      (node (ref "Q1") (pin "3") (pinfunction "D_3") (pintype "passive"))
    )
    (net (code "18") (name "Net-(-M2-P)") (class "Default")
      (node (ref "-M2") (pin "1") (pinfunction "P_1") (pintype "passive"))
      (node (ref "C23") (pin "1") (pinfunction "1_1") (pintype "passive"))
      (node (ref "Q2") (pin "3") (pinfunction "D_3") (pintype "passive"))
    )
    (net (code "19") (name "Net-(-M3-P)") (class "Default")
      (node (ref "-M3") (pin "1") (pinfunction "P_1") (pintype "passive"))
      (node (ref "C33") (pin "1") (pinfunction "1_1") (pintype "passive"))
      (node (ref "Q3") (pin "3") (pinfunction "D_3") (pintype "passive"))
    )
    (net (code "20") (name "Net-(-M4-P)") (class "Default")
      (node (ref "-M4") (pin "1") (pinfunction "P_1") (pintype "passive"))
      (node (ref "C35") (pin "1") (pinfunction "1_1") (pintype "passive"))
      (node (ref "Q4") (pin "3") (pinfunction "D_3") (pintype "passive"))
    )
    (net (code "21") (name "Net-(C9-Pad1)") (class "Default")
      (node (ref "C9") (pin "1") (pinfunction "1_1") (pintype "passive"))
      (node (ref "U$3") (pin "2") (pinfunction "2_2") (pintype "passive"))
    )
    (net (code "22") (name "Net-(D1-PadA)") (class "Default")
      (node (ref "D1") (pin "A") (pinfunction "A_A") (pintype "passive"))
      (node (ref "R6") (pin "2") (pinfunction "2_2") (pintype "passive"))
    )
    (net (code "23") (name "Net-(D2-PadA)") (class "Default")
      (node (ref "D2") (pin "A") (pinfunction "A_A") (pintype "passive"))
      (node (ref "R1") (pin "2") (pinfunction "2_2") (pintype "passive"))
    )
    (net (code "24") (name "Net-(D3-PadA)") (class "Default")
      (node (ref "D3") (pin "A") (pinfunction "A_A") (pintype "passive"))
      (node (ref "R19") (pin "2") (pinfunction "2_2") (pintype "passive"))
    )
    (net (code "25") (name "Net-(D4-PadA)") (class "Default")
      (node (ref "D4") (pin "A") (pinfunction "A_A") (pintype "passive"))
      (node (ref "R20") (pin "2") (pinfunction "2_2") (pintype "passive"))
    )
    (net (code "26") (name "Net-(E1-SIGNAL)") (class "Default")
      (node (ref "C10") (pin "2") (pinfunction "2_2") (pintype "passive"))
      (node (ref "C9") (pin "2") (pinfunction "2_2") (pintype "passive"))
      (node (ref "E1") (pin "ANT") (pinfunction "SIGNAL_ANT") (pintype "bidirectional"))
    )
    (net (code "27") (name "Net-(Q1-G)") (class "Default")
      (node (ref "Q1") (pin "1") (pinfunction "G_1") (pintype "passive"))
      (node (ref "R11") (pin "2") (pinfunction "2_2") (pintype "passive"))
      (node (ref "R12") (pin "1") (pinfunction "1_1") (pintype "passive"))
    )
    (net (code "28") (name "Net-(Q2-G)") (class "Default")
      (node (ref "Q2") (pin "1") (pinfunction "G_1") (pintype "passive"))
      (node (ref "R13") (pin "2") (pinfunction "2_2") (pintype "passive"))
      (node (ref "R14") (pin "1") (pinfunction "1_1") (pintype "passive"))
    )
    (net (code "29") (name "Net-(Q3-G)") (class "Default")
      (node (ref "Q3") (pin "1") (pinfunction "G_1") (pintype "passive"))
      (node (ref "R15") (pin "2") (pinfunction "2_2") (pintype "passive"))
      (node (ref "R16") (pin "1") (pinfunction "1_1") (pintype "passive"))
    )
    (net (code "30") (name "Net-(Q4-G)") (class "Default")
      (node (ref "Q4") (pin "1") (pinfunction "G_1") (pintype "passive"))
      (node (ref "R17") (pin "2") (pinfunction "2_2") (pintype "passive"))
      (node (ref "R18") (pin "1") (pinfunction "1_1") (pintype "passive"))
    )
    (net (code "31") (name "Net-(U2-CPOUT)") (class "Default")
      (node (ref "C6") (pin "1") (pinfunction "1_1") (pintype "passive"))
      (node (ref "U2") (pin "20") (pinfunction "CPOUT_20") (pintype "output"))
    )
    (net (code "32") (name "Net-(U2-REGOUT)") (class "Default")
      (node (ref "C3") (pin "1") (pinfunction "1_1") (pintype "passive"))
      (node (ref "U2") (pin "10") (pinfunction "REGOUT_10") (pintype "passive"))
    )
    (net (code "33") (name "Net-(U4-DVDD)") (class "Default")
      (node (ref "C13") (pin "1") (pinfunction "1_1") (pintype "passive"))
      (node (ref "U4") (pin "19") (pinfunction "DVDD_19") (pintype "power_in"))
    )
    (net (code "34") (name "Net-(U4-IREF)") (class "Default")
      (node (ref "R2") (pin "1") (pinfunction "1_1") (pintype "passive"))
      (node (ref "U4") (pin "16") (pinfunction "IREF_16") (pintype "input"))
    )
    (net (code "35") (name "Net-(U4-XC1)") (class "Default")
      (node (ref "C7") (pin "1") (pinfunction "1_1") (pintype "passive"))
      (node (ref "R4") (pin "1") (pinfunction "1_1") (pintype "passive"))
      (node (ref "U4") (pin "10") (pinfunction "XC1_10") (pintype "input"))
      (node (ref "Y3") (pin "3") (pinfunction "2_3") (pintype "passive"))
    )
    (net (code "36") (name "Net-(U4-XC2)") (class "Default")
      (node (ref "C8") (pin "1") (pinfunction "1_1") (pintype "passive"))
      (node (ref "R4") (pin "2") (pinfunction "2_2") (pintype "passive"))
      (node (ref "U4") (pin "9") (pinfunction "XC2_9") (pintype "output"))
      (node (ref "Y3") (pin "1") (pinfunction "1_1") (pintype "passive"))
    )
    (net (code "37") (name "OSC32_IN") (class "Default")
      (node (ref "C30") (pin "1") (pinfunction "1_1") (pintype "passive"))
      (node (ref "U1") (pin "3") (pinfunction "PC14-OSC32_IN_3") (pintype "bidirectional"))
      (node (ref "Y4") (pin "P$1") (pinfunction "1_P$1") (pintype "passive"))
    )
    (net (code "38") (name "OSC32_OUT") (class "Default")
      (node (ref "C31") (pin "1") (pinfunction "1_1") (pintype "passive"))
      (node (ref "U1") (pin "4") (pinfunction "PC15-OSC32_OUT_4") (pintype "bidirectional"))
      (node (ref "Y4") (pin "P$2") (pinfunction "2_P$2") (pintype "passive"))
    )
    (net (code "39") (name "OSC_IN") (class "Default")
      (node (ref "C16") (pin "1") (pinfunction "1_1") (pintype "passive"))
      (node (ref "R3") (pin "2") (pinfunction "2_2") (pintype "passive"))
      (node (ref "U1") (pin "5") (pinfunction "PD0_OSC_IN_5") (pintype "bidirectional"))
      (node (ref "Y1") (pin "1") (pinfunction "1_1") (pintype "passive"))
    )
    (net (code "40") (name "OSC_OUT") (class "Default")
      (node (ref "C17") (pin "1") (pinfunction "1_1") (pintype "passive"))
      (node (ref "R3") (pin "1") (pinfunction "1_1") (pintype "passive"))
      (node (ref "U1") (pin "6") (pinfunction "PD1_OSC_OUT_6") (pintype "bidirectional"))
      (node (ref "Y1") (pin "3") (pinfunction "2_3") (pintype "passive"))
    )
    (net (code "41") (name "RESET") (class "Default")
      (node (ref "C22") (pin "1") (pinfunction "1_1") (pintype "passive"))
      (node (ref "R5") (pin "1") (pinfunction "1_1") (pintype "passive"))
      (node (ref "S2") (pin "1") (pinfunction "1_1") (pintype "passive"))
      (node (ref "U1") (pin "7") (pinfunction "NRST_7") (pintype "input"))
    )
    (net (code "42") (name "SCK") (class "Default")
      (node (ref "+M22") (pin "1") (pinfunction "P_1") (pintype "passive"))
      (node (ref "U1") (pin "15") (pinfunction "PA5_15") (pintype "bidirectional"))
      (node (ref "U4") (pin "3") (pinfunction "SCK_3") (pintype "input"))
    )
    (net (code "43") (name "SCL1") (class "Default")
      (node (ref "+M6") (pin "1") (pinfunction "P_1") (pintype "passive"))
      (node (ref "R7") (pin "1") (pinfunction "1_1") (pintype "passive"))
      (node (ref "U1") (pin "42") (pinfunction "PB6_42") (pintype "bidirectional"))
      (node (ref "U2") (pin "23") (pinfunction "SCL_23") (pintype "bidirectional"))
      (node (ref "U6") (pin "2") (pinfunction "SCK_2") (pintype "input"))
    )
    (net (code "44") (name "SDA1") (class "Default")
      (node (ref "+M5") (pin "1") (pinfunction "P_1") (pintype "passive"))
      (node (ref "R8") (pin "1") (pinfunction "1_1") (pintype "passive"))
      (node (ref "U1") (pin "43") (pinfunction "PB7_43") (pintype "bidirectional"))
      (node (ref "U2") (pin "24") (pinfunction "SDA_24") (pintype "bidirectional"))
      (node (ref "U6") (pin "4") (pinfunction "SDI_4") (pintype "bidirectional"))
    )
    (net (code "45") (name "SWCLK") (class "Default")
      (node (ref "J2") (pin "2") (pinfunction "2_2") (pintype "passive"))
      (node (ref "U1") (pin "37") (pinfunction "PA14_37") (pintype "bidirectional"))
    )
    (net (code "46") (name "SWDIO") (class "Default")
      (node (ref "J2") (pin "3") (pinfunction "3_3") (pintype "passive"))
      (node (ref "U1") (pin "34") (pinfunction "PA13_34") (pintype "bidirectional"))
    )
    (net (code "47") (name "UART_RX") (class "Default")
      (node (ref "J1") (pin "2") (pinfunction "2_2") (pintype "passive"))
      (node (ref "U1") (pin "31") (pinfunction "PA10_31") (pintype "bidirectional"))
    )
    (net (code "48") (name "UART_TX") (class "Default")
      (node (ref "J1") (pin "3") (pinfunction "3_3") (pintype "passive"))
      (node (ref "U1") (pin "30") (pinfunction "PA9_30") (pintype "bidirectional"))
    )
    (net (code "49") (name "VDD") (class "Default")
      (node (ref "+M18") (pin "1") (pinfunction "P_1") (pintype "passive"))
      (node (ref "C14") (pin "1") (pinfunction "1_1") (pintype "passive"))
      (node (ref "C15") (pin "2") (pinfunction "2_2") (pintype "passive"))
      (node (ref "C18") (pin "1") (pinfunction "1_1") (pintype "passive"))
      (node (ref "C19") (pin "1") (pinfunction "1_1") (pintype "passive"))
      (node (ref "C20") (pin "1") (pinfunction "1_1") (pintype "passive"))
      (node (ref "C21") (pin "1") (pinfunction "1_1") (pintype "passive"))
      (node (ref "C25") (pin "1") (pinfunction "1_1") (pintype "passive"))
      (node (ref "C29") (pin "1") (pinfunction "1_1") (pintype "passive"))
      (node (ref "C4") (pin "1") (pinfunction "1_1") (pintype "passive"))
      (node (ref "C5") (pin "1") (pinfunction "1_1") (pintype "passive"))
      (node (ref "IC1") (pin "2") (pinfunction "VO_2") (pintype "passive"))
      (node (ref "J1") (pin "4") (pinfunction "4_4") (pintype "passive"))
      (node (ref "J2") (pin "4") (pinfunction "4_4") (pintype "passive"))
      (node (ref "R5") (pin "2") (pinfunction "2_2") (pintype "passive"))
      (node (ref "R6") (pin "1") (pinfunction "1_1") (pintype "passive"))
      (node (ref "R7") (pin "2") (pinfunction "2_2") (pintype "passive"))
      (node (ref "R8") (pin "2") (pinfunction "2_2") (pintype "passive"))
      (node (ref "U1") (pin "24") (pinfunction "VDD_24") (pintype "power_in"))
      (node (ref "U1") (pin "36") (pinfunction "VDD_36") (pintype "power_in"))
      (node (ref "U1") (pin "48") (pinfunction "VDD_48") (pintype "power_in"))
      (node (ref "U1") (pin "9") (pinfunction "VDDA_9") (pintype "power_in"))
      (node (ref "U2") (pin "13") (pinfunction "VDD_13") (pintype "power_in"))
      (node (ref "U2") (pin "8") (pinfunction "VLOGIC_8") (pintype "power_in"))
      (node (ref "U4") (pin "15") (pinfunction "VDD_15") (pintype "power_in"))
      (node (ref "U4") (pin "18") (pinfunction "VDD_18") (pintype "power_in"))
      (node (ref "U4") (pin "7") (pinfunction "VDD_7") (pintype "power_in"))
      (node (ref "U6") (pin "1") (pinfunction "VDDIO_1") (pintype "power_in"))
      (node (ref "U6") (pin "10") (pinfunction "VDD_10") (pintype "power_in"))
      (node (ref "U6") (pin "6") (pinfunction "CSB_6") (pintype "input"))
    )
    (net (code "50") (name "VDD_PA") (class "Default")
      (node (ref "C11") (pin "2") (pinfunction "2_2") (pintype "passive"))
      (node (ref "C12") (pin "2") (pinfunction "2_2") (pintype "passive"))
      (node (ref "U$2") (pin "2") (pinfunction "2_2") (pintype "passive"))
      (node (ref "U4") (pin "11") (pinfunction "VDD_PA_11") (pintype "power_in"))
    )
    (net (code "51") (name "VIN") (class "Default")
      (node (ref "+M1") (pin "1") (pinfunction "P_1") (pintype "passive"))
      (node (ref "+M2") (pin "1") (pinfunction "P_1") (pintype "passive"))
      (node (ref "+M3") (pin "1") (pinfunction "P_1") (pintype "passive"))
      (node (ref "+M4") (pin "1") (pinfunction "P_1") (pintype "passive"))
      (node (ref "C1") (pin "2") (pinfunction "2_2") (pintype "passive"))
      (node (ref "C2") (pin "2") (pinfunction "2_2") (pintype "passive"))
      (node (ref "C23") (pin "2") (pinfunction "2_2") (pintype "passive"))
      (node (ref "C24") (pin "1") (pinfunction "1_1") (pintype "passive"))
      (node (ref "C32") (pin "2") (pinfunction "2_2") (pintype "passive"))
      (node (ref "C33") (pin "2") (pinfunction "2_2") (pintype "passive"))
      (node (ref "C34") (pin "2") (pinfunction "2_2") (pintype "passive"))
      (node (ref "C35") (pin "2") (pinfunction "2_2") (pintype "passive"))
      (node (ref "C36") (pin "2") (pinfunction "2_2") (pintype "passive"))
      (node (ref "IC1") (pin "3") (pinfunction "VI_3") (pintype "input"))
      (node (ref "J3") (pin "2") (pinfunction "2_2") (pintype "passive"))
      (node (ref "R21") (pin "1") (pinfunction "1_1") (pintype "passive"))
    )
    (net (code "52") (name "unconnected-(U1-PA8-Pad29)") (class "Default")
      (node (ref "U1") (pin "29") (pinfunction "PA8_29") (pintype "bidirectional"))
    )
    (net (code "53") (name "unconnected-(U1-PA11-Pad32)") (class "Default")
      (node (ref "U1") (pin "32") (pinfunction "PA11_32") (pintype "bidirectional"))
    )
    (net (code "54") (name "unconnected-(U1-PB3-Pad39)") (class "Default")
      (node (ref "U1") (pin "39") (pinfunction "PB3_39") (pintype "bidirectional"))
    )
    (net (code "55") (name "unconnected-(U1-PB4-Pad40)") (class "Default")
      (node (ref "U1") (pin "40") (pinfunction "PB4_40") (pintype "bidirectional"))
    )
    (net (code "56") (name "unconnected-(U1-PB5-Pad41)") (class "Default")
      (node (ref "U1") (pin "41") (pinfunction "PB5_41") (pintype "bidirectional"))
    )
    (net (code "57") (name "unconnected-(U1-PB8-Pad45)") (class "Default")
      (node (ref "U1") (pin "45") (pinfunction "PB8_45") (pintype "bidirectional"))
    )
    (net (code "58") (name "unconnected-(U1-PB9-Pad46)") (class "Default")
      (node (ref "U1") (pin "46") (pinfunction "PB9_46") (pintype "bidirectional"))
    )
    (net (code "59") (name "unconnected-(U1-PB10-Pad21)") (class "Default")
      (node (ref "U1") (pin "21") (pinfunction "PB10_21") (pintype "bidirectional"))
    )
    (net (code "60") (name "unconnected-(U1-PB11-Pad22)") (class "Default")
      (node (ref "U1") (pin "22") (pinfunction "PB11_22") (pintype "bidirectional"))
    )
    (net (code "61") (name "unconnected-(U1-PB13-Pad26)") (class "Default")
      (node (ref "U1") (pin "26") (pinfunction "PB13_26") (pintype "bidirectional"))
    )
    (net (code "62") (name "unconnected-(U1-PB14-Pad27)") (class "Default")
      (node (ref "U1") (pin "27") (pinfunction "PB14_27") (pintype "bidirectional"))
    )
    (net (code "63") (name "unconnected-(U1-PB15-Pad28)") (class "Default")
      (node (ref "U1") (pin "28") (pinfunction "PB15_28") (pintype "bidirectional"))
    )
    (net (code "64") (name "unconnected-(U1-VBAT-Pad1)") (class "Default")
      (node (ref "U1") (pin "1") (pinfunction "VBAT_1") (pintype "bidirectional"))
    )
    (net (code "65") (name "unconnected-(U2-AUX_CL-Pad7)") (class "Default")
      (node (ref "U2") (pin "7") (pinfunction "AUX_CL_7") (pintype "bidirectional"))
    )
    (net (code "66") (name "unconnected-(U2-AUX_DA-Pad6)") (class "Default")
      (node (ref "U2") (pin "6") (pinfunction "AUX_DA_6") (pintype "bidirectional"))
    )
    (net (code "67") (name "unconnected-(U2-INT-Pad12)") (class "Default")
      (node (ref "U2") (pin "12") (pinfunction "INT_12") (pintype "output"))
    )
    (net (code "68") (name "unconnected-(U2-NC_2-Pad2)") (class "Default")
      (node (ref "U2") (pin "2") (pinfunction "NC_2_2") (pintype "passive"))
    )
    (net (code "69") (name "unconnected-(U2-NC_3-Pad3)") (class "Default")
      (node (ref "U2") (pin "3") (pinfunction "NC_3_3") (pintype "passive"))
    )
    (net (code "70") (name "unconnected-(U2-NC_4-Pad4)") (class "Default")
      (node (ref "U2") (pin "4") (pinfunction "NC_4_4") (pintype "passive"))
    )
    (net (code "71") (name "unconnected-(U2-NC_5-Pad5)") (class "Default")
      (node (ref "U2") (pin "5") (pinfunction "NC_5_5") (pintype "passive"))
    )
    (net (code "72") (name "unconnected-(U2-NC_14-Pad14)") (class "Default")
      (node (ref "U2") (pin "14") (pinfunction "NC_14_14") (pintype "passive"))
    )
    (net (code "73") (name "unconnected-(U2-NC_15-Pad15)") (class "Default")
      (node (ref "U2") (pin "15") (pinfunction "NC_15_15") (pintype "passive"))
    )
    (net (code "74") (name "unconnected-(U2-NC_16-Pad16)") (class "Default")
      (node (ref "U2") (pin "16") (pinfunction "NC_16_16") (pintype "passive"))
    )
    (net (code "75") (name "unconnected-(U2-NC_17-Pad17)") (class "Default")
      (node (ref "U2") (pin "17") (pinfunction "NC_17_17") (pintype "passive"))
    )
    (net (code "76") (name "unconnected-(U2-RESV_19-Pad19)") (class "Default")
      (node (ref "U2") (pin "19") (pinfunction "RESV_19_19") (pintype "passive"))
    )
    (net (code "77") (name "unconnected-(U2-RESV_21-Pad21)") (class "Default")
      (node (ref "U2") (pin "21") (pinfunction "RESV_21_21") (pintype "passive"))
    )
    (net (code "78") (name "unconnected-(U2-RESV_22-Pad22)") (class "Default")
      (node (ref "U2") (pin "22") (pinfunction "RESV_22_22") (pintype "passive"))
    )
    (net (code "79") (name "unconnected-(U6-INT-Pad7)") (class "Default")
      (node (ref "U6") (pin "7") (pinfunction "INT_7") (pintype "output"))
    )
  )
)
